# 03_GAP_MEM.net
KiCad netlist of a schematic drawn in Altium Designer
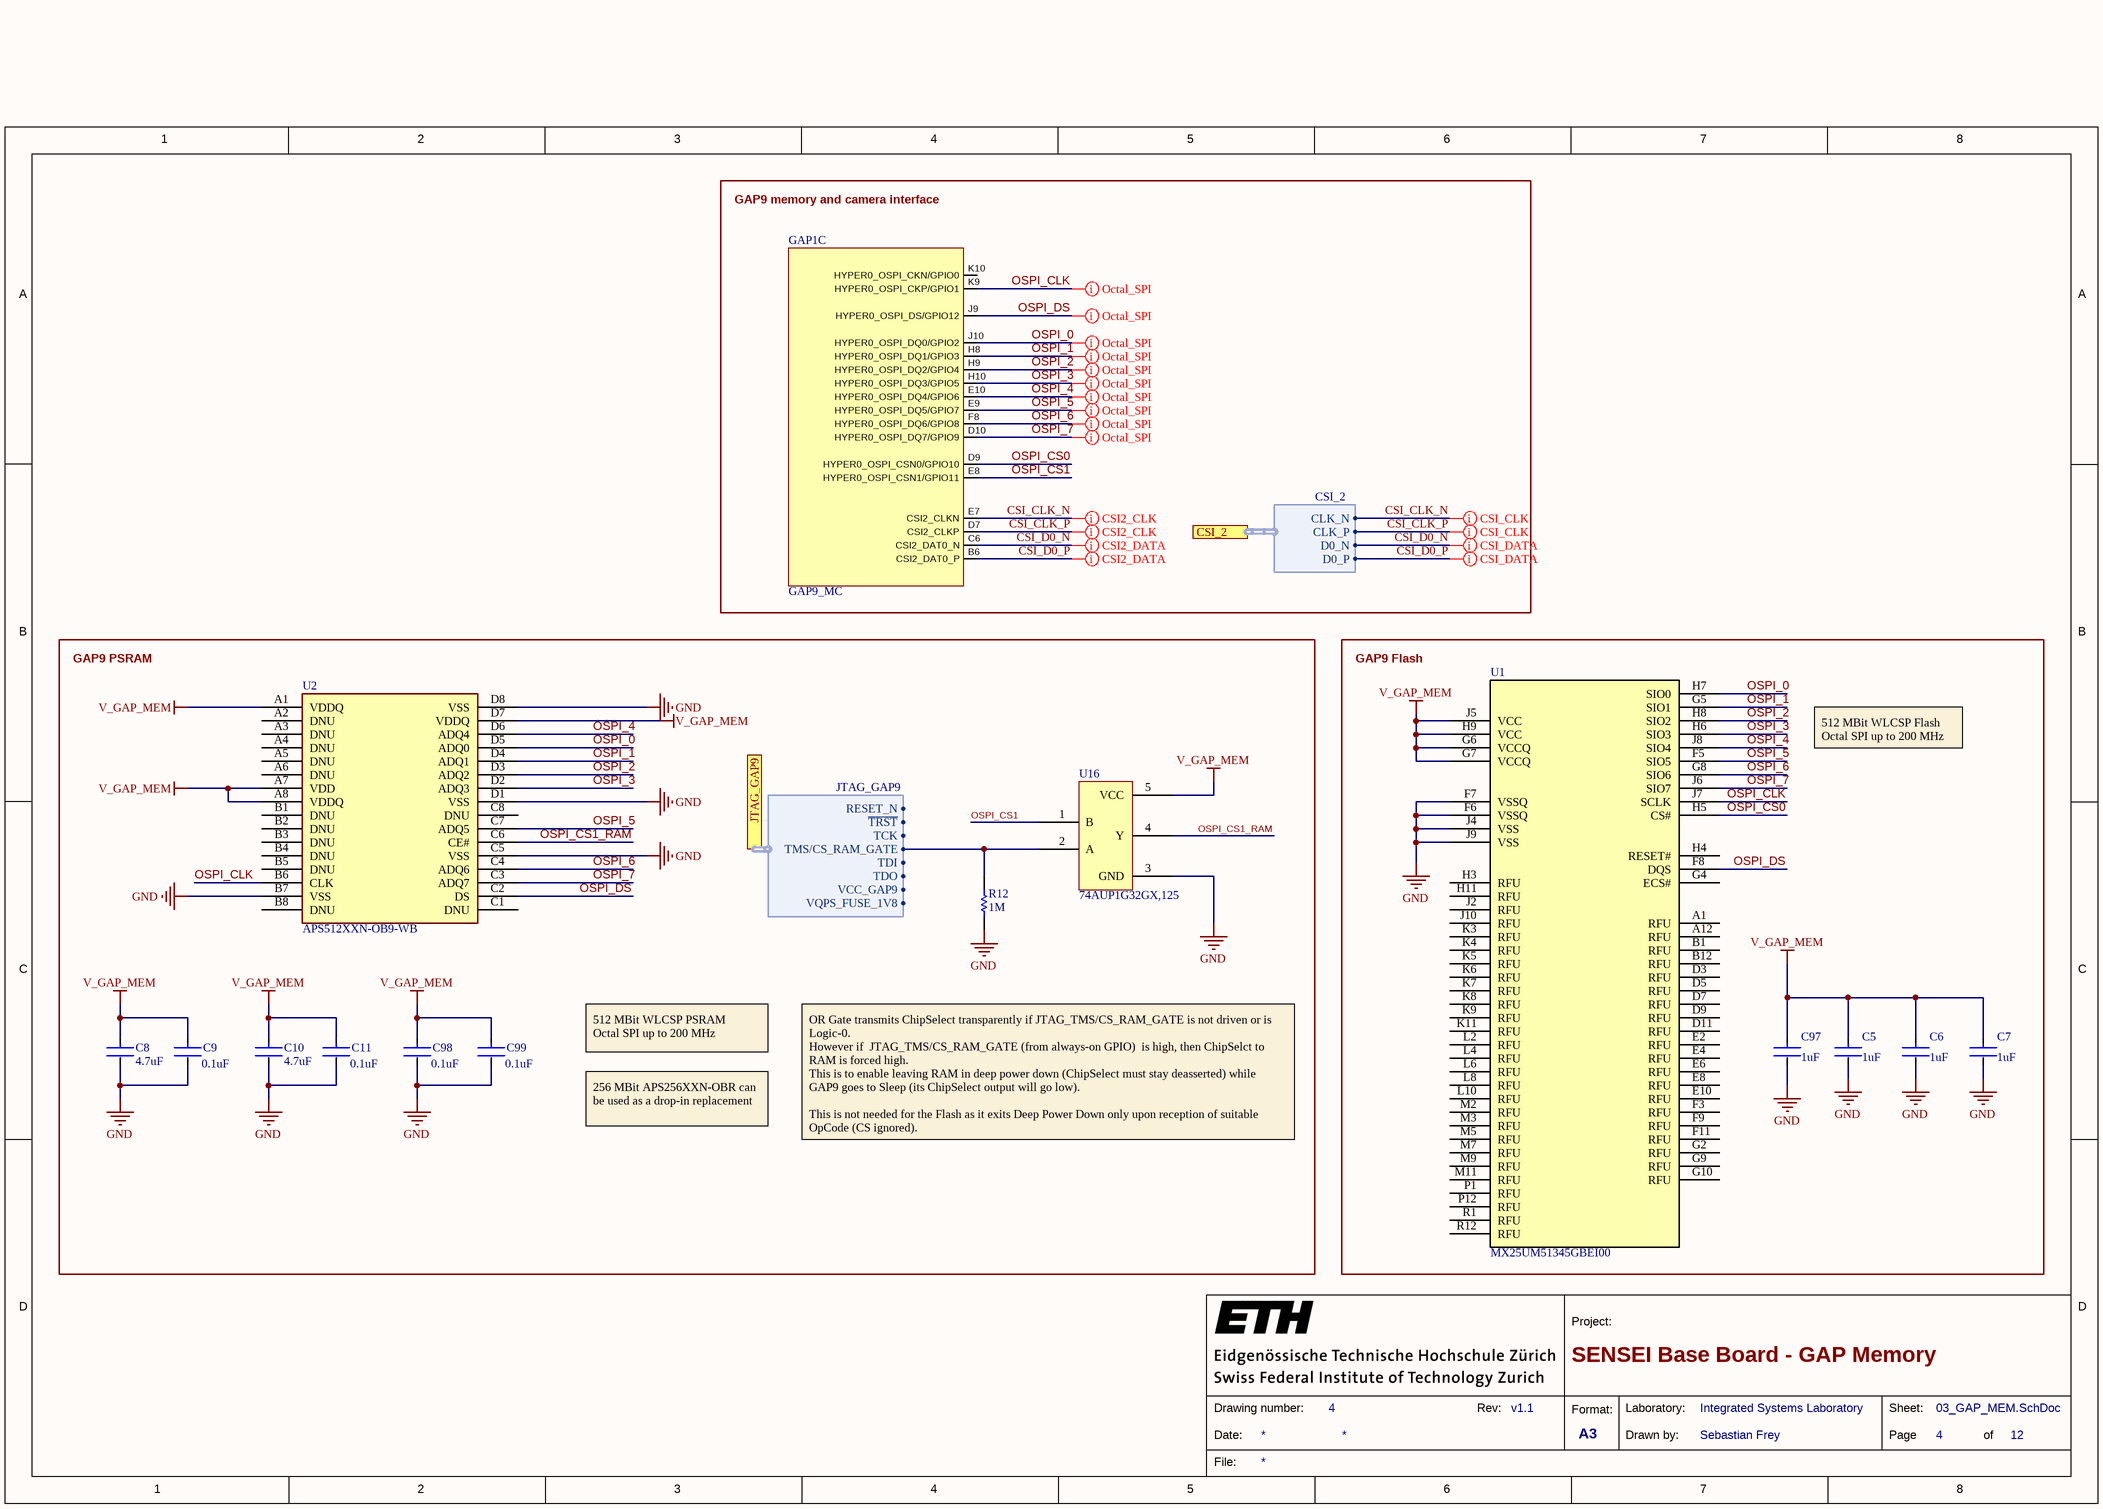
[diagram p0: 03_GAP_MEM.SchDoc]

(export (version "E")
  (design (tool "Eeschema 10.0.6"))
  (components
    (comp (ref "C5")
      (value "CL03A105KP3NSNC")
      (footprint "FP-CL03-IPC_C")
      (description "Cap Ceramic 1uF 10V X5R ±10% Pad SMD 0201 +85°C T/R")
      (fields (field (name "TOLERANCE") "10%") (field (name "CAPACITANCE") "1uF"))
      (libsource (lib "Altium Content Vault") (part "b4654b650e69147ec39a6b967a45e02"))
    )
    (comp (ref "C6")
      (value "CL03A105KP3NSNC")
      (footprint "FP-CL03-IPC_C")
      (description "Cap Ceramic 1uF 10V X5R ±10% Pad SMD 0201 +85°C T/R")
      (fields (field (name "TOLERANCE") "10%") (field (name "CAPACITANCE") "1uF"))
      (libsource (lib "Altium Content Vault") (part "b4654b650e69147ec39a6b967a45e02"))
    )
    (comp (ref "C7")
      (value "CL03A105KP3NSNC")
      (footprint "FP-CL03-IPC_C")
      (description "Cap Ceramic 1uF 10V X5R ±10% Pad SMD 0201 +85°C T/R")
      (fields (field (name "TOLERANCE") "10%") (field (name "CAPACITANCE") "1uF"))
      (libsource (lib "Altium Content Vault") (part "b4654b650e69147ec39a6b967a45e02"))
    )
    (comp (ref "C8")
      (value "C1005X5R0J475K050BC")
      (footprint "FP-C1005-050-0_15-IPC_C")
      (description "CAP CER 4.7UF 6.3V X5R 0402")
      (fields
        (field (name "VOLTAGE") "6.3V")
        (field (name "CAPACITANCE") "4.7uF")
        (field (name "TOLERANCE") "10%")
      )
      (libsource (lib "Altium Content Vault") (part "02cd4be3c70576c341d710602a673aa"))
    )
    (comp (ref "C9")
      (value "GRM033Z71C104KE14D")
      (footprint "FP-GRM033-0_03-IPC_C")
      (description "Chip Multilayer Ceramic Capacitors for General Purpose, 0201, 0.10uF, X7R, 15%, 10%, 16V")
      (fields (field (name "CAPACITANCE") "0.1uF"))
      (libsource (lib "Altium Content Vault") (part "b4654b650e69147ec39a6b967a45e02"))
    )
    (comp (ref "C10")
      (value "C1005X5R0J475K050BC")
      (footprint "FP-C1005-050-0_15-IPC_C")
      (description "CAP CER 4.7UF 6.3V X5R 0402")
      (fields
        (field (name "VOLTAGE") "6.3V")
        (field (name "CAPACITANCE") "4.7uF")
        (field (name "TOLERANCE") "10%")
      )
      (libsource (lib "Altium Content Vault") (part "02cd4be3c70576c341d710602a673aa"))
    )
    (comp (ref "C11")
      (value "GRM033Z71C104KE14D")
      (footprint "FP-GRM033-0_03-IPC_C")
      (description "Chip Multilayer Ceramic Capacitors for General Purpose, 0201, 0.10uF, X7R, 15%, 10%, 16V")
      (fields (field (name "CAPACITANCE") "0.1uF"))
      (libsource (lib "Altium Content Vault") (part "b4654b650e69147ec39a6b967a45e02"))
    )
    (comp (ref "C97")
      (value "CL03A105KP3NSNC")
      (footprint "FP-CL03-IPC_C")
      (description "Cap Ceramic 1uF 10V X5R ±10% Pad SMD 0201 +85°C T/R")
      (fields (field (name "TOLERANCE") "10%") (field (name "CAPACITANCE") "1uF"))
      (libsource (lib "Altium Content Vault") (part "b4654b650e69147ec39a6b967a45e02"))
    )
    (comp (ref "C98")
      (value "GRM033Z71C104KE14D")
      (footprint "FP-GRM033-0_03-IPC_C")
      (description "Chip Multilayer Ceramic Capacitors for General Purpose, 0201, 0.10uF, X7R, 15%, 10%, 16V")
      (fields (field (name "CAPACITANCE") "0.1uF"))
      (libsource (lib "Altium Content Vault") (part "b4654b650e69147ec39a6b967a45e02"))
    )
    (comp (ref "C99")
      (value "GRM033Z71C104KE14D")
      (footprint "FP-GRM033-0_03-IPC_C")
      (description "Chip Multilayer Ceramic Capacitors for General Purpose, 0201, 0.10uF, X7R, 15%, 10%, 16V")
      (fields (field (name "CAPACITANCE") "0.1uF"))
      (libsource (lib "Altium Content Vault") (part "b4654b650e69147ec39a6b967a45e02"))
    )
    (comp (ref "GAP1")
      (value "GAP9_MC")
      (footprint "EEG_PcbLib:GAP9")
      (libsource (lib "EEG_SchLib") (part "GAP9_MC"))
    )
    (comp (ref "R12")
      (value "1M")
      (footprint "RESC0201(0603)_L")
      (description "1M 0.05W 5% 0201 (0603 Metric)  SMD")
      (fields (field (name "TOLERANCE") "5 %") (field (name "POWER") "0.05 W"))
      (libsource (lib "Altium Content Vault") (part "RES"))
    )
    (comp (ref "U1")
      (value "MX25UM51345GBEI00")
      (footprint "EEG_PcbLib:MX25UM51345GBEI00")
      (description "Macronix 512 Mbit WLCSP Flash")
      (libsource (lib "EEG_SchLib") (part "MX25UM51345GBEI00"))
    )
    (comp (ref "U2")
      (value "APS512XXN-OB9-WB")
      (footprint "EEG_PcbLib:WLCSP32_APS512XXN-OB9-WB")
      (description "512 Mbit octal SPI PSRAM APmemory")
      (fields (field (name "COPYRIGHT") "Copyright (C) 2022 Ultra Librarian. All rights reserved."))
      (libsource (lib "EEG_SchLib") (part "APS512XXN-OB9-WB"))
    )
    (comp (ref "U16")
      (value "74AUP1G32GX,125")
      (footprint "EEG_PcbLib:SOT1226-3")
      (libsource (lib "EEG_SchLib") (part "74AUP1G32GX,125"))
    )
  )
  (nets
    (net (code "3") (name "/CSI_CLK_N") (class "Default")
      (node (ref "GAP1") (pin "E7") (pinfunction "CSI2_CLKN_E7") (pintype "passive"))
    )
    (net (code "4") (name "/CSI_CLK_P") (class "Default")
      (node (ref "GAP1") (pin "D7") (pinfunction "CSI2_CLKP_D7") (pintype "passive"))
    )
    (net (code "5") (name "/CSI_D0_N") (class "Default")
      (node (ref "GAP1") (pin "C6") (pinfunction "CSI2_DAT0_N_C6") (pintype "passive"))
    )
    (net (code "6") (name "/CSI_D0_P") (class "Default")
      (node (ref "GAP1") (pin "B6") (pinfunction "CSI2_DAT0_P_B6") (pintype "passive"))
    )
    (net (code "7") (name "/OSPI_0") (class "Default")
      (node (ref "GAP1") (pin "J10") (pinfunction "HYPER0_OSPI_DQ0/GPIO2_J10") (pintype "passive"))
      (node (ref "U1") (pin "H7") (pinfunction "SIO0_H7") (pintype "passive"))
      (node (ref "U2") (pin "D5") (pinfunction "ADQ0_D5") (pintype "passive"))
    )
    (net (code "8") (name "/OSPI_1") (class "Default")
      (node (ref "GAP1") (pin "H8") (pinfunction "HYPER0_OSPI_DQ1/GPIO3_H8") (pintype "passive"))
      (node (ref "U1") (pin "G5") (pinfunction "SIO1_G5") (pintype "passive"))
      (node (ref "U2") (pin "D4") (pinfunction "ADQ1_D4") (pintype "passive"))
    )
    (net (code "9") (name "/OSPI_2") (class "Default")
      (node (ref "GAP1") (pin "H9") (pinfunction "HYPER0_OSPI_DQ2/GPIO4_H9") (pintype "passive"))
      (node (ref "U1") (pin "H8") (pinfunction "SIO2_H8") (pintype "passive"))
      (node (ref "U2") (pin "D3") (pinfunction "ADQ2_D3") (pintype "passive"))
    )
    (net (code "10") (name "/OSPI_3") (class "Default")
      (node (ref "GAP1") (pin "H10") (pinfunction "HYPER0_OSPI_DQ3/GPIO5_H10") (pintype "passive"))
      (node (ref "U1") (pin "H6") (pinfunction "SIO3_H6") (pintype "passive"))
      (node (ref "U2") (pin "D2") (pinfunction "ADQ3_D2") (pintype "passive"))
    )
    (net (code "11") (name "/OSPI_4") (class "Default")
      (node (ref "GAP1") (pin "E10") (pinfunction "HYPER0_OSPI_DQ4/GPIO6_E10") (pintype "passive"))
      (node (ref "U1") (pin "J8") (pinfunction "SIO4_J8") (pintype "passive"))
      (node (ref "U2") (pin "D6") (pinfunction "ADQ4_D6") (pintype "passive"))
    )
    (net (code "12") (name "/OSPI_5") (class "Default")
      (node (ref "GAP1") (pin "E9") (pinfunction "HYPER0_OSPI_DQ5/GPIO7_E9") (pintype "passive"))
      (node (ref "U1") (pin "F5") (pinfunction "SIO5_F5") (pintype "passive"))
      (node (ref "U2") (pin "C7") (pinfunction "ADQ5_C7") (pintype "passive"))
    )
    (net (code "13") (name "/OSPI_6") (class "Default")
      (node (ref "GAP1") (pin "F8") (pinfunction "HYPER0_OSPI_DQ6/GPIO8_F8") (pintype "passive"))
      (node (ref "U1") (pin "G8") (pinfunction "SIO6_G8") (pintype "passive"))
      (node (ref "U2") (pin "C4") (pinfunction "ADQ6_C4") (pintype "passive"))
    )
    (net (code "14") (name "/OSPI_7") (class "Default")
      (node (ref "GAP1") (pin "D10") (pinfunction "HYPER0_OSPI_DQ7/GPIO9_D10") (pintype "passive"))
      (node (ref "U1") (pin "J6") (pinfunction "SIO7_J6") (pintype "passive"))
      (node (ref "U2") (pin "C3") (pinfunction "ADQ7_C3") (pintype "passive"))
    )
    (net (code "15") (name "/OSPI_CLK") (class "Default")
      (node (ref "GAP1") (pin "K9") (pinfunction "HYPER0_OSPI_CKP/GPIO1_K9") (pintype "passive"))
      (node (ref "U1") (pin "J7") (pinfunction "SCLK_J7") (pintype "passive"))
      (node (ref "U2") (pin "B6") (pinfunction "CLK_B6") (pintype "passive"))
    )
    (net (code "16") (name "/OSPI_CS0") (class "Default")
      (node (ref "GAP1") (pin "D9") (pinfunction "HYPER0_OSPI_CSN0/GPIO10_D9") (pintype "passive"))
      (node (ref "U1") (pin "H5") (pinfunction "CS#_H5") (pintype "passive"))
    )
    (net (code "17") (name "/OSPI_CS1") (class "Default")
      (node (ref "GAP1") (pin "E8") (pinfunction "HYPER0_OSPI_CSN1/GPIO11_E8") (pintype "passive"))
      (node (ref "U16") (pin "1") (pinfunction "B_1") (pintype "passive"))
    )
    (net (code "18") (name "/OSPI_CS1_RAM") (class "Default")
      (node (ref "U16") (pin "4") (pinfunction "Y_4") (pintype "passive"))
      (node (ref "U2") (pin "C6") (pinfunction "CE#_C6") (pintype "passive"))
    )
    (net (code "19") (name "/OSPI_DS") (class "Default")
      (node (ref "GAP1") (pin "J9") (pinfunction "HYPER0_OSPI_DS/GPIO12_J9") (pintype "passive"))
      (node (ref "U1") (pin "F8") (pinfunction "DQS_F8") (pintype "passive"))
      (node (ref "U2") (pin "C2") (pinfunction "DS_C2") (pintype "passive"))
    )
    (net (code "22") (name "GND") (class "Default")
      (node (ref "C10") (pin "2") (pinfunction "2_2") (pintype "passive"))
      (node (ref "C11") (pin "2") (pinfunction "2_2") (pintype "passive"))
      (node (ref "C5") (pin "2") (pinfunction "2_2") (pintype "passive"))
      (node (ref "C6") (pin "2") (pinfunction "2_2") (pintype "passive"))
      (node (ref "C7") (pin "2") (pinfunction "2_2") (pintype "passive"))
      (node (ref "C8") (pin "2") (pinfunction "2_2") (pintype "passive"))
      (node (ref "C9") (pin "2") (pinfunction "2_2") (pintype "passive"))
      (node (ref "C97") (pin "2") (pinfunction "2_2") (pintype "passive"))
      (node (ref "C98") (pin "2") (pinfunction "2_2") (pintype "passive"))
      (node (ref "C99") (pin "2") (pinfunction "2_2") (pintype "passive"))
      (node (ref "R12") (pin "1") (pinfunction "1_1") (pintype "passive"))
      (node (ref "U1") (pin "F6") (pinfunction "VSSQ_F6") (pintype "passive"))
      (node (ref "U1") (pin "F7") (pinfunction "VSSQ_F7") (pintype "passive"))
      (node (ref "U1") (pin "J4") (pinfunction "VSS_J4") (pintype "passive"))
      (node (ref "U1") (pin "J9") (pinfunction "VSS_J9") (pintype "passive"))
      (node (ref "U16") (pin "3") (pinfunction "GND_3") (pintype "power_in"))
      (node (ref "U2") (pin "B7") (pinfunction "VSS_B7") (pintype "passive"))
      (node (ref "U2") (pin "C5") (pinfunction "VSS_C5") (pintype "passive"))
      (node (ref "U2") (pin "D1") (pinfunction "VSS_D1") (pintype "passive"))
      (node (ref "U2") (pin "D8") (pinfunction "VSS_D8") (pintype "passive"))
    )
    (net (code "23") (name "Net-(U16-A)") (class "Default")
      (node (ref "R12") (pin "2") (pinfunction "2_2") (pintype "passive"))
      (node (ref "U16") (pin "2") (pinfunction "A_2") (pintype "passive"))
    )
    (net (code "24") (name "V_GAP_MEM") (class "Default")
      (node (ref "C10") (pin "1") (pinfunction "1_1") (pintype "passive"))
      (node (ref "C11") (pin "1") (pinfunction "1_1") (pintype "passive"))
      (node (ref "C5") (pin "1") (pinfunction "1_1") (pintype "passive"))
      (node (ref "C6") (pin "1") (pinfunction "1_1") (pintype "passive"))
      (node (ref "C7") (pin "1") (pinfunction "1_1") (pintype "passive"))
      (node (ref "C8") (pin "1") (pinfunction "1_1") (pintype "passive"))
      (node (ref "C9") (pin "1") (pinfunction "1_1") (pintype "passive"))
      (node (ref "C97") (pin "1") (pinfunction "1_1") (pintype "passive"))
      (node (ref "C98") (pin "1") (pinfunction "1_1") (pintype "passive"))
      (node (ref "C99") (pin "1") (pinfunction "1_1") (pintype "passive"))
      (node (ref "U1") (pin "G6") (pinfunction "VCCQ_G6") (pintype "passive"))
      (node (ref "U1") (pin "G7") (pinfunction "VCCQ_G7") (pintype "passive"))
      (node (ref "U1") (pin "H9") (pinfunction "VCC_H9") (pintype "passive"))
      (node (ref "U1") (pin "J5") (pinfunction "VCC_J5") (pintype "passive"))
      (node (ref "U16") (pin "5") (pinfunction "VCC_5") (pintype "power_in"))
      (node (ref "U2") (pin "A1") (pinfunction "VDDQ_A1") (pintype "passive"))
      (node (ref "U2") (pin "A7") (pinfunction "VDD_A7") (pintype "passive"))
      (node (ref "U2") (pin "A8") (pinfunction "VDDQ_A8") (pintype "passive"))
      (node (ref "U2") (pin "D7") (pinfunction "VDDQ_D7") (pintype "passive"))
    )
    (net (code "25") (name "unconnected-(GAP1C-HYPER0_OSPI_CKN{slash}GPIO0-PadK10)") (class "Default")
      (node (ref "GAP1") (pin "K10") (pinfunction "HYPER0_OSPI_CKN/GPIO0_K10") (pintype "passive"))
    )
    (net (code "26") (name "unconnected-(U1-ECS#-PadG4)") (class "Default")
      (node (ref "U1") (pin "G4") (pinfunction "ECS#_G4") (pintype "passive"))
    )
    (net (code "27") (name "unconnected-(U1-RESET#-PadH4)") (class "Default")
      (node (ref "U1") (pin "H4") (pinfunction "RESET#_H4") (pintype "passive"))
    )
    (net (code "28") (name "unconnected-(U1-RFU-PadA1)") (class "Default")
      (node (ref "U1") (pin "A1") (pinfunction "RFU_A1") (pintype "passive"))
    )
    (net (code "29") (name "unconnected-(U1-RFU-PadA12)") (class "Default")
      (node (ref "U1") (pin "A12") (pinfunction "RFU_A12") (pintype "passive"))
    )
    (net (code "30") (name "unconnected-(U1-RFU-PadB1)") (class "Default")
      (node (ref "U1") (pin "B1") (pinfunction "RFU_B1") (pintype "passive"))
    )
    (net (code "31") (name "unconnected-(U1-RFU-PadB12)") (class "Default")
      (node (ref "U1") (pin "B12") (pinfunction "RFU_B12") (pintype "passive"))
    )
    (net (code "32") (name "unconnected-(U1-RFU-PadD3)") (class "Default")
      (node (ref "U1") (pin "D3") (pinfunction "RFU_D3") (pintype "passive"))
    )
    (net (code "33") (name "unconnected-(U1-RFU-PadD5)") (class "Default")
      (node (ref "U1") (pin "D5") (pinfunction "RFU_D5") (pintype "passive"))
    )
    (net (code "34") (name "unconnected-(U1-RFU-PadD7)") (class "Default")
      (node (ref "U1") (pin "D7") (pinfunction "RFU_D7") (pintype "passive"))
    )
    (net (code "35") (name "unconnected-(U1-RFU-PadD9)") (class "Default")
      (node (ref "U1") (pin "D9") (pinfunction "RFU_D9") (pintype "passive"))
    )
    (net (code "36") (name "unconnected-(U1-RFU-PadD11)") (class "Default")
      (node (ref "U1") (pin "D11") (pinfunction "RFU_D11") (pintype "passive"))
    )
    (net (code "37") (name "unconnected-(U1-RFU-PadE2)") (class "Default")
      (node (ref "U1") (pin "E2") (pinfunction "RFU_E2") (pintype "passive"))
    )
    (net (code "38") (name "unconnected-(U1-RFU-PadE4)") (class "Default")
      (node (ref "U1") (pin "E4") (pinfunction "RFU_E4") (pintype "passive"))
    )
    (net (code "39") (name "unconnected-(U1-RFU-PadE6)") (class "Default")
      (node (ref "U1") (pin "E6") (pinfunction "RFU_E6") (pintype "passive"))
    )
    (net (code "40") (name "unconnected-(U1-RFU-PadE8)") (class "Default")
      (node (ref "U1") (pin "E8") (pinfunction "RFU_E8") (pintype "passive"))
    )
    (net (code "41") (name "unconnected-(U1-RFU-PadE10)") (class "Default")
      (node (ref "U1") (pin "E10") (pinfunction "RFU_E10") (pintype "passive"))
    )
    (net (code "42") (name "unconnected-(U1-RFU-PadF3)") (class "Default")
      (node (ref "U1") (pin "F3") (pinfunction "RFU_F3") (pintype "passive"))
    )
    (net (code "43") (name "unconnected-(U1-RFU-PadF9)") (class "Default")
      (node (ref "U1") (pin "F9") (pinfunction "RFU_F9") (pintype "passive"))
    )
    (net (code "44") (name "unconnected-(U1-RFU-PadF11)") (class "Default")
      (node (ref "U1") (pin "F11") (pinfunction "RFU_F11") (pintype "passive"))
    )
    (net (code "45") (name "unconnected-(U1-RFU-PadG2)") (class "Default")
      (node (ref "U1") (pin "G2") (pinfunction "RFU_G2") (pintype "passive"))
    )
    (net (code "46") (name "unconnected-(U1-RFU-PadG9)") (class "Default")
      (node (ref "U1") (pin "G9") (pinfunction "RFU_G9") (pintype "passive"))
    )
    (net (code "47") (name "unconnected-(U1-RFU-PadG10)") (class "Default")
      (node (ref "U1") (pin "G10") (pinfunction "RFU_G10") (pintype "passive"))
    )
    (net (code "48") (name "unconnected-(U1-RFU-PadH3)") (class "Default")
      (node (ref "U1") (pin "H3") (pinfunction "RFU_H3") (pintype "passive"))
    )
    (net (code "49") (name "unconnected-(U1-RFU-PadH11)") (class "Default")
      (node (ref "U1") (pin "H11") (pinfunction "RFU_H11") (pintype "passive"))
    )
    (net (code "50") (name "unconnected-(U1-RFU-PadJ2)") (class "Default")
      (node (ref "U1") (pin "J2") (pinfunction "RFU_J2") (pintype "passive"))
    )
    (net (code "51") (name "unconnected-(U1-RFU-PadJ10)") (class "Default")
      (node (ref "U1") (pin "J10") (pinfunction "RFU_J10") (pintype "passive"))
    )
    (net (code "52") (name "unconnected-(U1-RFU-PadK3)") (class "Default")
      (node (ref "U1") (pin "K3") (pinfunction "RFU_K3") (pintype "passive"))
    )
    (net (code "53") (name "unconnected-(U1-RFU-PadK4)") (class "Default")
      (node (ref "U1") (pin "K4") (pinfunction "RFU_K4") (pintype "passive"))
    )
    (net (code "54") (name "unconnected-(U1-RFU-PadK5)") (class "Default")
      (node (ref "U1") (pin "K5") (pinfunction "RFU_K5") (pintype "passive"))
    )
    (net (code "55") (name "unconnected-(U1-RFU-PadK6)") (class "Default")
      (node (ref "U1") (pin "K6") (pinfunction "RFU_K6") (pintype "passive"))
    )
    (net (code "56") (name "unconnected-(U1-RFU-PadK7)") (class "Default")
      (node (ref "U1") (pin "K7") (pinfunction "RFU_K7") (pintype "passive"))
    )
    (net (code "57") (name "unconnected-(U1-RFU-PadK8)") (class "Default")
      (node (ref "U1") (pin "K8") (pinfunction "RFU_K8") (pintype "passive"))
    )
    (net (code "58") (name "unconnected-(U1-RFU-PadK9)") (class "Default")
      (node (ref "U1") (pin "K9") (pinfunction "RFU_K9") (pintype "passive"))
    )
    (net (code "59") (name "unconnected-(U1-RFU-PadK11)") (class "Default")
      (node (ref "U1") (pin "K11") (pinfunction "RFU_K11") (pintype "passive"))
    )
    (net (code "60") (name "unconnected-(U1-RFU-PadL2)") (class "Default")
      (node (ref "U1") (pin "L2") (pinfunction "RFU_L2") (pintype "passive"))
    )
    (net (code "61") (name "unconnected-(U1-RFU-PadL4)") (class "Default")
      (node (ref "U1") (pin "L4") (pinfunction "RFU_L4") (pintype "passive"))
    )
    (net (code "62") (name "unconnected-(U1-RFU-PadL6)") (class "Default")
      (node (ref "U1") (pin "L6") (pinfunction "RFU_L6") (pintype "passive"))
    )
    (net (code "63") (name "unconnected-(U1-RFU-PadL8)") (class "Default")
      (node (ref "U1") (pin "L8") (pinfunction "RFU_L8") (pintype "passive"))
    )
    (net (code "64") (name "unconnected-(U1-RFU-PadL10)") (class "Default")
      (node (ref "U1") (pin "L10") (pinfunction "RFU_L10") (pintype "passive"))
    )
    (net (code "65") (name "unconnected-(U1-RFU-PadM2)") (class "Default")
      (node (ref "U1") (pin "M2") (pinfunction "RFU_M2") (pintype "passive"))
    )
    (net (code "66") (name "unconnected-(U1-RFU-PadM3)") (class "Default")
      (node (ref "U1") (pin "M3") (pinfunction "RFU_M3") (pintype "passive"))
    )
    (net (code "67") (name "unconnected-(U1-RFU-PadM5)") (class "Default")
      (node (ref "U1") (pin "M5") (pinfunction "RFU_M5") (pintype "passive"))
    )
    (net (code "68") (name "unconnected-(U1-RFU-PadM7)") (class "Default")
      (node (ref "U1") (pin "M7") (pinfunction "RFU_M7") (pintype "passive"))
    )
    (net (code "69") (name "unconnected-(U1-RFU-PadM9)") (class "Default")
      (node (ref "U1") (pin "M9") (pinfunction "RFU_M9") (pintype "passive"))
    )
    (net (code "70") (name "unconnected-(U1-RFU-PadM11)") (class "Default")
      (node (ref "U1") (pin "M11") (pinfunction "RFU_M11") (pintype "passive"))
    )
    (net (code "71") (name "unconnected-(U1-RFU-PadP1)") (class "Default")
      (node (ref "U1") (pin "P1") (pinfunction "RFU_P1") (pintype "passive"))
    )
    (net (code "72") (name "unconnected-(U1-RFU-PadP12)") (class "Default")
      (node (ref "U1") (pin "P12") (pinfunction "RFU_P12") (pintype "passive"))
    )
    (net (code "73") (name "unconnected-(U1-RFU-PadR1)") (class "Default")
      (node (ref "U1") (pin "R1") (pinfunction "RFU_R1") (pintype "passive"))
    )
    (net (code "74") (name "unconnected-(U1-RFU-PadR12)") (class "Default")
      (node (ref "U1") (pin "R12") (pinfunction "RFU_R12") (pintype "passive"))
    )
    (net (code "75") (name "unconnected-(U2-DNU-PadA2)") (class "Default")
      (node (ref "U2") (pin "A2") (pinfunction "DNU_A2") (pintype "passive"))
    )
    (net (code "76") (name "unconnected-(U2-DNU-PadA3)") (class "Default")
      (node (ref "U2") (pin "A3") (pinfunction "DNU_A3") (pintype "passive"))
    )
    (net (code "77") (name "unconnected-(U2-DNU-PadA4)") (class "Default")
      (node (ref "U2") (pin "A4") (pinfunction "DNU_A4") (pintype "passive"))
    )
    (net (code "78") (name "unconnected-(U2-DNU-PadA5)") (class "Default")
      (node (ref "U2") (pin "A5") (pinfunction "DNU_A5") (pintype "passive"))
    )
    (net (code "79") (name "unconnected-(U2-DNU-PadA6)") (class "Default")
      (node (ref "U2") (pin "A6") (pinfunction "DNU_A6") (pintype "passive"))
    )
    (net (code "80") (name "unconnected-(U2-DNU-PadB1)") (class "Default")
      (node (ref "U2") (pin "B1") (pinfunction "DNU_B1") (pintype "passive"))
    )
    (net (code "81") (name "unconnected-(U2-DNU-PadB2)") (class "Default")
      (node (ref "U2") (pin "B2") (pinfunction "DNU_B2") (pintype "passive"))
    )
    (net (code "82") (name "unconnected-(U2-DNU-PadB3)") (class "Default")
      (node (ref "U2") (pin "B3") (pinfunction "DNU_B3") (pintype "passive"))
    )
    (net (code "83") (name "unconnected-(U2-DNU-PadB4)") (class "Default")
      (node (ref "U2") (pin "B4") (pinfunction "DNU_B4") (pintype "passive"))
    )
    (net (code "84") (name "unconnected-(U2-DNU-PadB5)") (class "Default")
      (node (ref "U2") (pin "B5") (pinfunction "DNU_B5") (pintype "passive"))
    )
    (net (code "85") (name "unconnected-(U2-DNU-PadB8)") (class "Default")
      (node (ref "U2") (pin "B8") (pinfunction "DNU_B8") (pintype "passive"))
    )
    (net (code "86") (name "unconnected-(U2-DNU-PadC1)") (class "Default")
      (node (ref "U2") (pin "C1") (pinfunction "DNU_C1") (pintype "passive"))
    )
    (net (code "87") (name "unconnected-(U2-DNU-PadC8)") (class "Default")
      (node (ref "U2") (pin "C8") (pinfunction "DNU_C8") (pintype "passive"))
    )
  )
)
